# Input_Sense_Network.net
KiCad netlist of a schematic drawn in Altium Designer
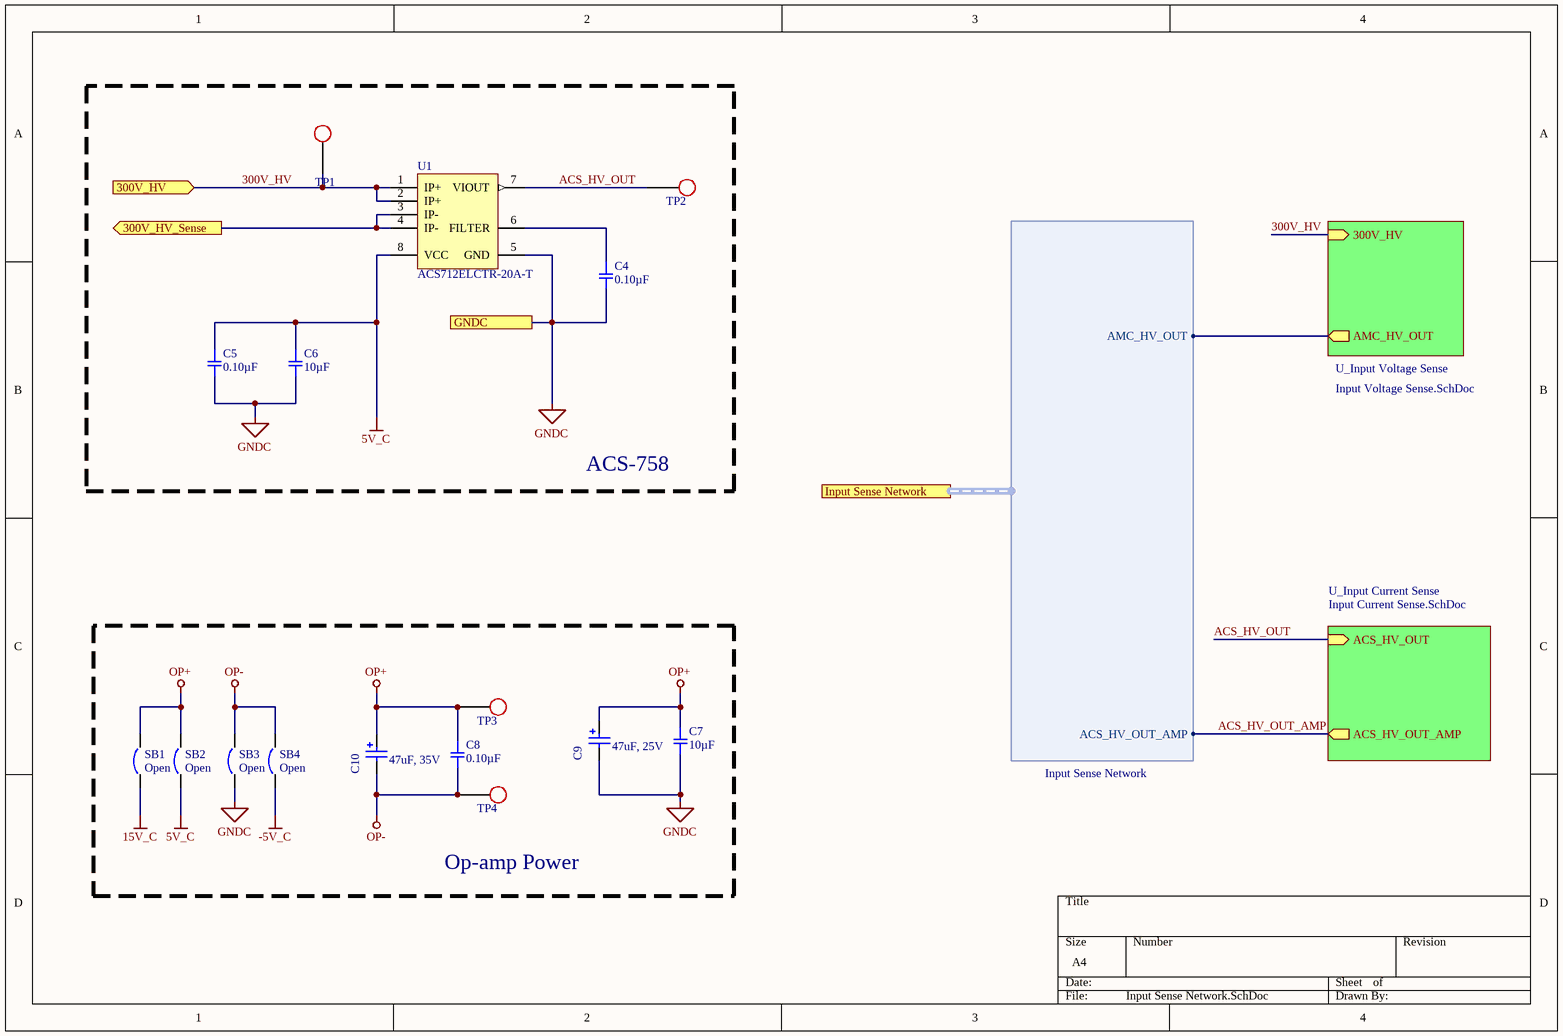
[diagram p0: Input Sense Network.SchDoc]

(export (version "E")
  (design (tool "Eeschema 10.0.6"))
  (components
    (comp (ref "C4")
      (value "0.10µF")
      (footprint "SMD-0805C")
      (description "CAP CER 0.1UF 50V X7R 0805")
      (fields
        (field (name "DIGI-KEY PART NUMBER") "490-11955-1-ND")
        (field (name "PART NUMBER") "GCD21BR71H104KA01L")
      )
      (libsource (lib "capacitor_murata_0805") (part "GCD21BR71H104KA01L"))
    )
    (comp (ref "C5")
      (value "0.10µF")
      (footprint "SMD-0805C")
      (description "CAP CER 0.1UF 50V X7R 0805")
      (fields
        (field (name "DIGI-KEY PART NUMBER") "490-11955-1-ND")
        (field (name "PART NUMBER") "GCD21BR71H104KA01L")
      )
      (libsource (lib "capacitor_murata_0805") (part "GCD21BR71H104KA01L"))
    )
    (comp (ref "C6")
      (value "10µF")
      (footprint "SMD-0805C")
      (description "CAP CER 10UF 10V X7R 0805")
      (fields
        (field (name "DIGI-KEY PART NUMBER") "490-12646-1-ND")
        (field (name "PART NUMBER") "GCJ21BR71A106KE01L")
      )
      (libsource (lib "capacitor_murata_0805") (part "GCJ21BR71A106KE01L"))
    )
    (comp (ref "C7")
      (value "10µF")
      (footprint "SMD-0805C")
      (description "CAP CER 10UF 10V X7R 0805")
      (fields
        (field (name "DIGI-KEY PART NUMBER") "490-12646-1-ND")
        (field (name "PART NUMBER") "GCJ21BR71A106KE01L")
      )
      (libsource (lib "capacitor_murata_0805") (part "GCJ21BR71A106KE01L"))
    )
    (comp (ref "C8")
      (value "0.10µF")
      (footprint "SMD-0805C")
      (description "CAP CER 0.1UF 50V X7R 0805")
      (fields
        (field (name "DIGI-KEY PART NUMBER") "490-11955-1-ND")
        (field (name "PART NUMBER") "GCD21BR71H104KA01L")
      )
      (libsource (lib "capacitor_murata_0805") (part "GCD21BR71H104KA01L"))
    )
    (comp (ref "C9")
      (value "47uF, 25V")
      (footprint "WCAP-ASLU_6.3x7.7")
      (description "WCAP-ASLU Aluminium Electrolytic Capacitors, D6.3mm x L7.7mm, 47uF, +/-20%, 25VDC")
      (fields (field (name "PART NUMBER") "865090445006") (field (name "PUBLISHER") "Wurth Elektronik"))
      (libsource (lib "Altium_WCAP-ASLU_SMD") (part "865090445006"))
    )
    (comp (ref "C10")
      (value "47uF, 35V")
      (footprint "WCAP-ASLL_6.3x5.5")
      (description "WCAP-ASLL SMT Aluminum Electrolytic Capacitors, D6.3mm x L5.5mm, 47uF, +/-20%, 35VDC")
      (fields (field (name "PART NUMBER") "865060543005") (field (name "PUBLISHER") "Wurth Elektronik"))
      (libsource (lib "Altium_WCAP-ASLL_SMD") (part "865060543005"))
    )
    (comp (ref "SB1")
      (value "Open")
      (footprint "0805-Solder Bridge")
      (description "Circuit Breaker")
      (fields (field (name "PUBLISHER") "Altium Limited"))
      (libsource (lib "Edge_Card_Ucc28951") (part "Solder Bridge"))
    )
    (comp (ref "SB2")
      (value "Open")
      (footprint "0805-Solder Bridge")
      (description "Circuit Breaker")
      (fields (field (name "PUBLISHER") "Altium Limited"))
      (libsource (lib "Edge_Card_Ucc28951") (part "Solder Bridge"))
    )
    (comp (ref "SB3")
      (value "Open")
      (footprint "0805-Solder Bridge")
      (description "Circuit Breaker")
      (fields (field (name "PUBLISHER") "Altium Limited"))
      (libsource (lib "Edge_Card_Ucc28951") (part "Solder Bridge"))
    )
    (comp (ref "SB4")
      (value "Open")
      (footprint "0805-Solder Bridge")
      (description "Circuit Breaker")
      (fields (field (name "PUBLISHER") "Altium Limited"))
      (libsource (lib "Edge_Card_Ucc28951") (part "Solder Bridge"))
    )
    (comp (ref "TP1")
      (value "Test Point")
      (footprint "Test_point_THT")
      (description "TP")
      (libsource (lib "PFC_Stage") (part "Test Point"))
    )
    (comp (ref "TP2")
      (value "Test Point")
      (footprint "Test_point_THT")
      (description "TP")
      (libsource (lib "PFC_Stage") (part "Test Point"))
    )
    (comp (ref "TP3")
      (value "Test Point")
      (footprint "Test_point_THT")
      (description "TP")
      (libsource (lib "PFC_Stage") (part "Test Point"))
    )
    (comp (ref "TP4")
      (value "Test Point")
      (footprint "Test_point_THT")
      (description "TP")
      (libsource (lib "PFC_Stage") (part "Test Point"))
    )
    (comp (ref "U1")
      (value "ACS712ELCTR-20A-T")
      (footprint "SOIC127P570X175_HS-9N")
      (fields (field (name "MANUFACTURER") "Allegro Microsystems"))
      (libsource (lib "Power Board UCC28951") (part "ACS712"))
    )
  )
  (nets
    (net (code "4") (name "-5V_C") (class "Default")
      (node (ref "SB4") (pin "1") (pinfunction "1_1") (pintype "passive"))
    )
    (net (code "5") (name "/300V_HV") (class "Default")
      (node (ref "TP1") (pin "1") (pinfunction "1_1") (pintype "passive"))
      (node (ref "U1") (pin "1") (pinfunction "IP+_1") (pintype "passive"))
      (node (ref "U1") (pin "2") (pinfunction "IP+_2") (pintype "passive"))
    )
    (net (code "6") (name "/300V_HV_Sense") (class "Default")
      (node (ref "U1") (pin "3") (pinfunction "IP-_3") (pintype "passive"))
      (node (ref "U1") (pin "4") (pinfunction "IP-_4") (pintype "passive"))
    )
    (net (code "7") (name "/ACS_HV_OUT") (class "Default")
      (node (ref "TP2") (pin "1") (pinfunction "1_1") (pintype "passive"))
      (node (ref "U1") (pin "7") (pinfunction "VIOUT_7") (pintype "output"))
    )
    (net (code "11") (name "5V_C") (class "Default")
      (node (ref "C5") (pin "1") (pinfunction "1_1") (pintype "passive"))
      (node (ref "C6") (pin "1") (pinfunction "1_1") (pintype "passive"))
      (node (ref "SB2") (pin "1") (pinfunction "1_1") (pintype "passive"))
      (node (ref "U1") (pin "8") (pinfunction "VCC_8") (pintype "power_in"))
    )
    (net (code "12") (name "15V_C") (class "Default")
      (node (ref "SB1") (pin "1") (pinfunction "1_1") (pintype "passive"))
    )
    (net (code "13") (name "GNDC") (class "Default")
      (node (ref "C4") (pin "2") (pinfunction "2_2") (pintype "passive"))
      (node (ref "C5") (pin "2") (pinfunction "2_2") (pintype "passive"))
      (node (ref "C6") (pin "2") (pinfunction "2_2") (pintype "passive"))
      (node (ref "C7") (pin "2") (pinfunction "2_2") (pintype "passive"))
      (node (ref "C9") (pin "1") (pinfunction "N_1") (pintype "passive"))
      (node (ref "SB3") (pin "1") (pinfunction "1_1") (pintype "passive"))
      (node (ref "U1") (pin "5") (pinfunction "GND_5") (pintype "power_in"))
    )
    (net (code "14") (name "Net-(U1-FILTER)") (class "Default")
      (node (ref "C4") (pin "1") (pinfunction "1_1") (pintype "passive"))
      (node (ref "U1") (pin "6") (pinfunction "FILTER_6") (pintype "passive"))
    )
    (net (code "15") (name "OP+") (class "Default")
      (node (ref "C10") (pin "2") (pinfunction "P_2") (pintype "passive"))
      (node (ref "C7") (pin "1") (pinfunction "1_1") (pintype "passive"))
      (node (ref "C8") (pin "1") (pinfunction "1_1") (pintype "passive"))
      (node (ref "C9") (pin "2") (pinfunction "P_2") (pintype "passive"))
      (node (ref "SB1") (pin "2") (pinfunction "2_2") (pintype "passive"))
      (node (ref "SB2") (pin "2") (pinfunction "2_2") (pintype "passive"))
      (node (ref "TP3") (pin "1") (pinfunction "1_1") (pintype "passive"))
    )
    (net (code "16") (name "OP-") (class "Default")
      (node (ref "C10") (pin "1") (pinfunction "N_1") (pintype "passive"))
      (node (ref "C8") (pin "2") (pinfunction "2_2") (pintype "passive"))
      (node (ref "SB3") (pin "2") (pinfunction "2_2") (pintype "passive"))
      (node (ref "SB4") (pin "2") (pinfunction "2_2") (pintype "passive"))
      (node (ref "TP4") (pin "1") (pinfunction "1_1") (pintype "passive"))
    )
  )
)
